# jtag-adapter-3-4.net
KiCad netlist of a schematic drawn in EAGLE
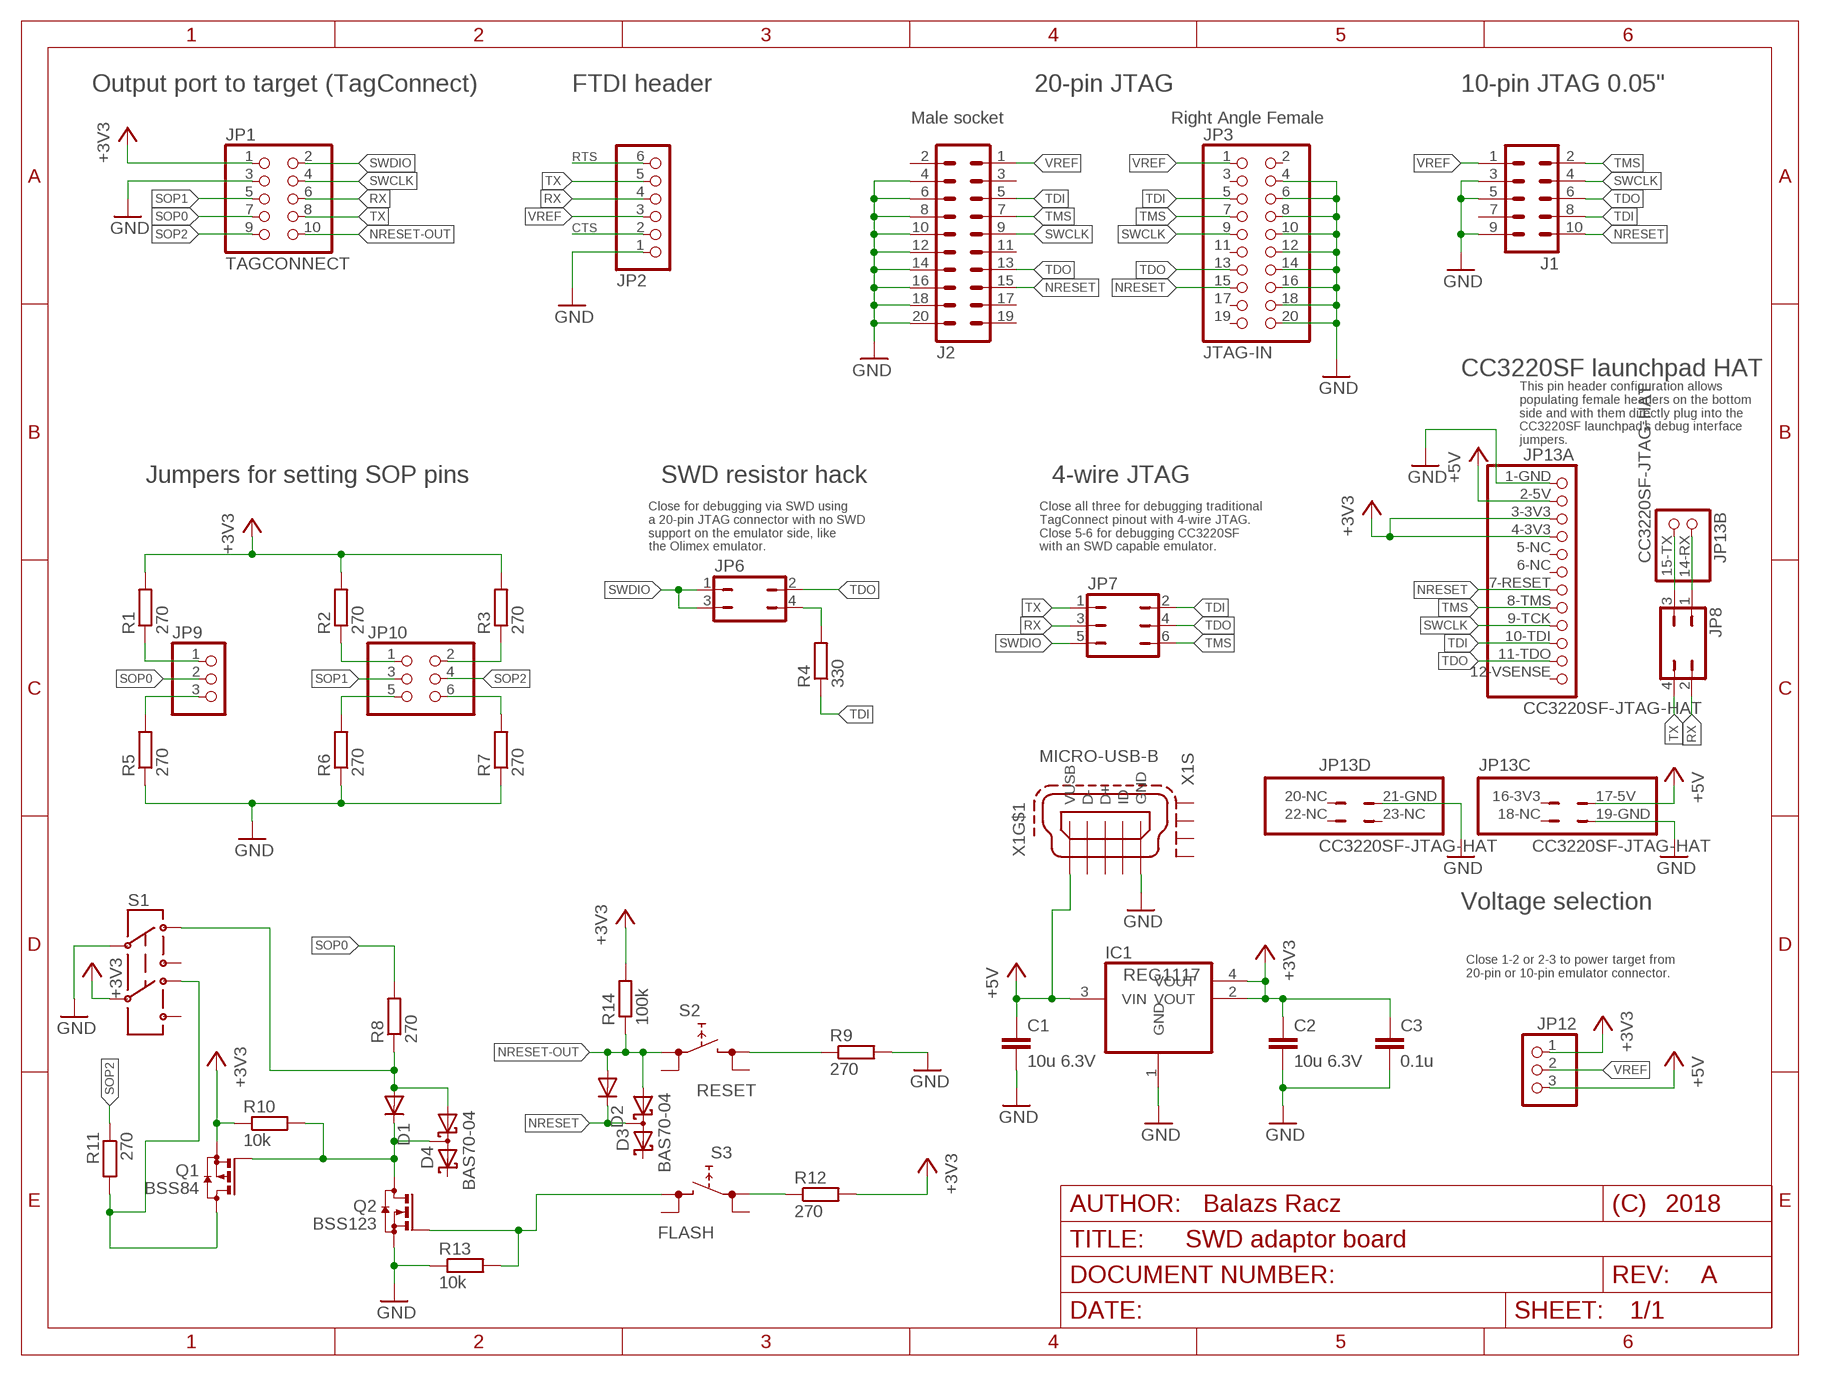
[diagram p0: schematic, sheet 1]

(export (version "E")
  (design (tool "Eeschema 10.0.6"))
  (components
    (comp (ref "C1")
      (value "10u 6.3V")
      (footprint "eagle-import:C0603K")
      (libsource (lib "eagle-import") (part "C-EUC0603K"))
    )
    (comp (ref "C2")
      (value "10u 6.3V")
      (footprint "eagle-import:C0603K")
      (libsource (lib "eagle-import") (part "C-EUC0603K"))
    )
    (comp (ref "C3")
      (value "0.1u")
      (footprint "eagle-import:C0603K")
      (libsource (lib "eagle-import") (part "C-EUC0603K"))
    )
    (comp (ref "D1")
      (value "DIODE-MINIMELF")
      (footprint "eagle-import:MINIMELF")
      (libsource (lib "eagle-import") (part "DIODE-MINIMELF"))
    )
    (comp (ref "D2")
      (value "DIODE-MINIMELF")
      (footprint "eagle-import:MINIMELF")
      (libsource (lib "eagle-import") (part "DIODE-MINIMELF"))
    )
    (comp (ref "D3")
      (value "BAS70-04")
      (footprint "eagle-import:SOT23")
      (libsource (lib "eagle-import") (part "BAS70-04"))
    )
    (comp (ref "D4")
      (value "BAS70-04")
      (footprint "eagle-import:SOT23")
      (libsource (lib "eagle-import") (part "BAS70-04"))
    )
    (comp (ref "IC1")
      (value "REG1117")
      (footprint "eagle-import:SOT223")
      (libsource (lib "eagle-import") (part "REG1117"))
    )
    (comp (ref "J1")
      (value "MA05-2_0.05X0.05")
      (footprint "eagle-import:MA05-2_0.05_X_0.05")
      (libsource (lib "eagle-import") (part "MA05-2_0.05X0.05"))
    )
    (comp (ref "J2")
      (value "MA10-2S")
      (footprint "eagle-import:MA10-2-SHROUDED")
      (libsource (lib "eagle-import") (part "MA10-2S"))
    )
    (comp (ref "JP1")
      (value "TAGCONNECT")
      (footprint "eagle-import:CON10M")
      (libsource (lib "eagle-import") (part "PINHD-2X5CN"))
    )
    (comp (ref "JP2")
      (value "PINHD-1X6")
      (footprint "eagle-import:1X06")
      (libsource (lib "eagle-import") (part "PINHD-1X6"))
    )
    (comp (ref "JP3")
      (value "JTAG-IN")
      (footprint "eagle-import:2X10")
      (libsource (lib "eagle-import") (part "PINHD-2X10"))
    )
    (comp (ref "JP6")
      (value "JP2Q")
      (footprint "eagle-import:JP2Q")
      (libsource (lib "eagle-import") (part "JP2Q"))
    )
    (comp (ref "JP7")
      (value "JP3Q")
      (footprint "eagle-import:JP3Q")
      (libsource (lib "eagle-import") (part "JP3Q"))
    )
    (comp (ref "JP8")
      (value "JP2Q")
      (footprint "eagle-import:JP2Q")
      (libsource (lib "eagle-import") (part "JP2Q"))
    )
    (comp (ref "JP9")
      (value "PINHD-1X3")
      (footprint "eagle-import:1X03")
      (libsource (lib "eagle-import") (part "PINHD-1X3"))
    )
    (comp (ref "JP10")
      (value "PINHD-2X3")
      (footprint "eagle-import:2X03")
      (libsource (lib "eagle-import") (part "PINHD-2X3"))
    )
    (comp (ref "JP12")
      (value "PINHD-1X3")
      (footprint "eagle-import:1X03")
      (libsource (lib "eagle-import") (part "PINHD-1X3"))
    )
    (comp (ref "JP13")
      (value "CC3220SF-JTAG-HAT")
      (footprint "eagle-import:JTAG-LAUNCHPAD-3220SF")
      (libsource (lib "eagle-import") (part "CC3220SF-JTAG-HAT"))
    )
    (comp (ref "Q1")
      (value "BSS84")
      (footprint "eagle-import:SOT23")
      (libsource (lib "eagle-import") (part "BSS84"))
    )
    (comp (ref "Q2")
      (value "BSS123")
      (footprint "eagle-import:SOT23")
      (libsource (lib "eagle-import") (part "BSS123"))
    )
    (comp (ref "R1")
      (value "270")
      (footprint "eagle-import:R0805")
      (libsource (lib "eagle-import") (part "R-EU_R0805"))
    )
    (comp (ref "R2")
      (value "270")
      (footprint "eagle-import:R0805")
      (libsource (lib "eagle-import") (part "R-EU_R0805"))
    )
    (comp (ref "R3")
      (value "270")
      (footprint "eagle-import:R0805")
      (libsource (lib "eagle-import") (part "R-EU_R0805"))
    )
    (comp (ref "R4")
      (value "330")
      (footprint "eagle-import:R0805")
      (libsource (lib "eagle-import") (part "R-EU_R0805"))
    )
    (comp (ref "R5")
      (value "270")
      (footprint "eagle-import:R0805")
      (libsource (lib "eagle-import") (part "R-EU_R0805"))
    )
    (comp (ref "R6")
      (value "270")
      (footprint "eagle-import:R0805")
      (libsource (lib "eagle-import") (part "R-EU_R0805"))
    )
    (comp (ref "R7")
      (value "270")
      (footprint "eagle-import:R0805")
      (libsource (lib "eagle-import") (part "R-EU_R0805"))
    )
    (comp (ref "R8")
      (value "270")
      (footprint "eagle-import:R0805")
      (libsource (lib "eagle-import") (part "R-EU_R0805"))
    )
    (comp (ref "R9")
      (value "270")
      (footprint "eagle-import:R0805")
      (libsource (lib "eagle-import") (part "R-EU_R0805"))
    )
    (comp (ref "R10")
      (value "10k")
      (footprint "eagle-import:R0805")
      (libsource (lib "eagle-import") (part "R-EU_R0805"))
    )
    (comp (ref "R11")
      (value "270")
      (footprint "eagle-import:R0805")
      (libsource (lib "eagle-import") (part "R-EU_R0805"))
    )
    (comp (ref "R12")
      (value "270")
      (footprint "eagle-import:R0805")
      (libsource (lib "eagle-import") (part "R-EU_R0805"))
    )
    (comp (ref "R13")
      (value "10k")
      (footprint "eagle-import:R0805")
      (libsource (lib "eagle-import") (part "R-EU_R0805"))
    )
    (comp (ref "R14")
      (value "100k")
      (footprint "eagle-import:R0805")
      (libsource (lib "eagle-import") (part "R-EU_R0805"))
    )
    (comp (ref "S1")
      (value "SWITCH-DPDTJS202011CQN")
      (footprint "eagle-import:DPDT-2.5X3.2MM")
      (libsource (lib "eagle-import") (part "SWITCH-DPDTJS202011CQN"))
    )
    (comp (ref "S2")
      (value "RESET")
      (footprint "eagle-import:TACTSW-6X6")
      (libsource (lib "eagle-import") (part "TACTSW-6X6S"))
    )
    (comp (ref "S3")
      (value "FLASH")
      (footprint "eagle-import:TACTSW-6X6")
      (libsource (lib "eagle-import") (part "TACTSW-6X6S"))
    )
    (comp (ref "X1")
      (value "MICRO-USB-B")
      (footprint "eagle-import:MICRO-B-PAC")
      (libsource (lib "eagle-import") (part "MICRO-USB-B"))
    )
  )
  (nets
    (net (code "1") (name "+3V3") (class "Default")
      (node (ref "C2") (pin "1") (pinfunction "1_1") (pintype "passive"))
      (node (ref "C3") (pin "1") (pinfunction "1_1") (pintype "passive"))
      (node (ref "IC1") (pin "2") (pinfunction "VOUT_2") (pintype "output"))
      (node (ref "IC1") (pin "4") (pinfunction "VOUT_4") (pintype "output"))
      (node (ref "JP1") (pin "1") (pinfunction "1_1") (pintype "passive"))
      (node (ref "JP12") (pin "1") (pinfunction "1_1") (pintype "passive"))
      (node (ref "JP13") (pin "3-3V3") (pinfunction "3_3-3V3") (pintype "passive"))
      (node (ref "JP13") (pin "4-3V3") (pinfunction "4_4-3V3") (pintype "passive"))
      (node (ref "Q1") (pin "2") (pinfunction "S_2") (pintype "passive"))
      (node (ref "R1") (pin "2") (pinfunction "2_2") (pintype "passive"))
      (node (ref "R10") (pin "1") (pinfunction "1_1") (pintype "passive"))
      (node (ref "R12") (pin "2") (pinfunction "2_2") (pintype "passive"))
      (node (ref "R14") (pin "2") (pinfunction "2_2") (pintype "passive"))
      (node (ref "R2") (pin "2") (pinfunction "2_2") (pintype "passive"))
      (node (ref "R3") (pin "2") (pinfunction "2_2") (pintype "passive"))
      (node (ref "S1") (pin "5") (pinfunction "2C_5") (pintype "bidirectional"))
    )
    (net (code "2") (name "+5V") (class "Default")
      (node (ref "C1") (pin "1") (pinfunction "1_1") (pintype "passive"))
      (node (ref "IC1") (pin "3") (pinfunction "VIN_3") (pintype "input"))
      (node (ref "JP12") (pin "3") (pinfunction "3_3") (pintype "passive"))
      (node (ref "JP13") (pin "17-5V") (pinfunction "2_17-5V") (pintype "passive"))
      (node (ref "JP13") (pin "2-5V") (pinfunction "2_2-5V") (pintype "passive"))
      (node (ref "X1") (pin "1") (pinfunction "VUSB_1") (pintype "passive"))
    )
    (net (code "3") (name "/CTS") (class "Default")
      (node (ref "JP2") (pin "2") (pinfunction "2_2") (pintype "passive"))
    )
    (net (code "4") (name "/RTS") (class "Default")
      (node (ref "JP2") (pin "6") (pinfunction "6_6") (pintype "passive"))
    )
    (net (code "5") (name "GND") (class "Default")
      (node (ref "C1") (pin "2") (pinfunction "2_2") (pintype "passive"))
      (node (ref "C2") (pin "2") (pinfunction "2_2") (pintype "passive"))
      (node (ref "C3") (pin "2") (pinfunction "2_2") (pintype "passive"))
      (node (ref "IC1") (pin "1") (pinfunction "GND_1") (pintype "power_in"))
      (node (ref "J1") (pin "3") (pinfunction "3_3") (pintype "passive"))
      (node (ref "J1") (pin "5") (pinfunction "5_5") (pintype "passive"))
      (node (ref "J1") (pin "9") (pinfunction "9_9") (pintype "passive"))
      (node (ref "J2") (pin "10") (pinfunction "10_10") (pintype "passive"))
      (node (ref "J2") (pin "12") (pinfunction "12_12") (pintype "passive"))
      (node (ref "J2") (pin "14") (pinfunction "14_14") (pintype "passive"))
      (node (ref "J2") (pin "16") (pinfunction "16_16") (pintype "passive"))
      (node (ref "J2") (pin "18") (pinfunction "18_18") (pintype "passive"))
      (node (ref "J2") (pin "20") (pinfunction "20_20") (pintype "passive"))
      (node (ref "J2") (pin "4") (pinfunction "4_4") (pintype "passive"))
      (node (ref "J2") (pin "6") (pinfunction "6_6") (pintype "passive"))
      (node (ref "J2") (pin "8") (pinfunction "8_8") (pintype "passive"))
      (node (ref "JP1") (pin "3") (pinfunction "3_3") (pintype "passive"))
      (node (ref "JP13") (pin "1-GND") (pinfunction "1_1-GND") (pintype "passive"))
      (node (ref "JP13") (pin "19-GND") (pinfunction "4_19-GND") (pintype "passive"))
      (node (ref "JP13") (pin "21-GND") (pinfunction "2_21-GND") (pintype "passive"))
      (node (ref "JP2") (pin "1") (pinfunction "1_1") (pintype "passive"))
      (node (ref "JP3") (pin "10") (pinfunction "10_10") (pintype "passive"))
      (node (ref "JP3") (pin "12") (pinfunction "12_12") (pintype "passive"))
      (node (ref "JP3") (pin "14") (pinfunction "14_14") (pintype "passive"))
      (node (ref "JP3") (pin "16") (pinfunction "16_16") (pintype "passive"))
      (node (ref "JP3") (pin "18") (pinfunction "18_18") (pintype "passive"))
      (node (ref "JP3") (pin "20") (pinfunction "20_20") (pintype "passive"))
      (node (ref "JP3") (pin "4") (pinfunction "4_4") (pintype "passive"))
      (node (ref "JP3") (pin "6") (pinfunction "6_6") (pintype "passive"))
      (node (ref "JP3") (pin "8") (pinfunction "8_8") (pintype "passive"))
      (node (ref "Q2") (pin "2") (pinfunction "S_2") (pintype "passive"))
      (node (ref "R13") (pin "1") (pinfunction "1_1") (pintype "passive"))
      (node (ref "R5") (pin "1") (pinfunction "1_1") (pintype "passive"))
      (node (ref "R6") (pin "1") (pinfunction "1_1") (pintype "passive"))
      (node (ref "R7") (pin "1") (pinfunction "1_1") (pintype "passive"))
      (node (ref "R9") (pin "2") (pinfunction "2_2") (pintype "passive"))
      (node (ref "S1") (pin "2") (pinfunction "1C_2") (pintype "bidirectional"))
      (node (ref "X1") (pin "5") (pinfunction "GND_5") (pintype "passive"))
    )
    (net (code "6") (name "NRESET") (class "Default")
      (node (ref "D2") (pin "C") (pinfunction "C_C") (pintype "passive"))
      (node (ref "D3") (pin "3") (pinfunction "C1A2_3") (pintype "passive"))
      (node (ref "J1") (pin "10") (pinfunction "10_10") (pintype "passive"))
      (node (ref "J2") (pin "15") (pinfunction "15_15") (pintype "passive"))
      (node (ref "JP13") (pin "7-RESET") (pinfunction "7_7-RESET") (pintype "passive"))
      (node (ref "JP3") (pin "15") (pinfunction "15_15") (pintype "passive"))
    )
    (net (code "7") (name "NRESET-OUT") (class "Default")
      (node (ref "D2") (pin "A") (pinfunction "A_A") (pintype "passive"))
      (node (ref "D3") (pin "1") (pinfunction "A1_1") (pintype "passive"))
      (node (ref "JP1") (pin "10") (pinfunction "10_10") (pintype "passive"))
      (node (ref "R14") (pin "1") (pinfunction "1_1") (pintype "passive"))
      (node (ref "S2") (pin "1") (pinfunction "1.1_1") (pintype "passive"))
    )
    (net (code "8") (name "Net-(D4-A1)") (class "Default")
      (node (ref "D1") (pin "A") (pinfunction "A_A") (pintype "passive"))
      (node (ref "D4") (pin "1") (pinfunction "A1_1") (pintype "passive"))
      (node (ref "R8") (pin "1") (pinfunction "1_1") (pintype "passive"))
      (node (ref "S1") (pin "1") (pinfunction "1A_1") (pintype "bidirectional"))
    )
    (net (code "9") (name "Net-(D4-C1A2)") (class "Default")
      (node (ref "D1") (pin "C") (pinfunction "C_C") (pintype "passive"))
      (node (ref "D4") (pin "3") (pinfunction "C1A2_3") (pintype "passive"))
      (node (ref "Q1") (pin "1") (pinfunction "G_1") (pintype "passive"))
      (node (ref "Q2") (pin "3") (pinfunction "D_3") (pintype "passive"))
      (node (ref "R10") (pin "2") (pinfunction "2_2") (pintype "passive"))
    )
    (net (code "10") (name "Net-(JP6-Pad4)") (class "Default")
      (node (ref "JP6") (pin "4") (pinfunction "4_4") (pintype "passive"))
      (node (ref "R4") (pin "2") (pinfunction "2_2") (pintype "passive"))
    )
    (net (code "11") (name "Net-(JP9-Pad1)") (class "Default")
      (node (ref "JP9") (pin "1") (pinfunction "1_1") (pintype "passive"))
      (node (ref "R1") (pin "1") (pinfunction "1_1") (pintype "passive"))
    )
    (net (code "12") (name "Net-(JP9-Pad3)") (class "Default")
      (node (ref "JP9") (pin "3") (pinfunction "3_3") (pintype "passive"))
      (node (ref "R5") (pin "2") (pinfunction "2_2") (pintype "passive"))
    )
    (net (code "13") (name "Net-(JP10-Pad1)") (class "Default")
      (node (ref "JP10") (pin "1") (pinfunction "1_1") (pintype "passive"))
      (node (ref "R2") (pin "1") (pinfunction "1_1") (pintype "passive"))
    )
    (net (code "14") (name "Net-(JP10-Pad2)") (class "Default")
      (node (ref "JP10") (pin "2") (pinfunction "2_2") (pintype "passive"))
      (node (ref "R3") (pin "1") (pinfunction "1_1") (pintype "passive"))
    )
    (net (code "15") (name "Net-(JP10-Pad5)") (class "Default")
      (node (ref "JP10") (pin "5") (pinfunction "5_5") (pintype "passive"))
      (node (ref "R6") (pin "2") (pinfunction "2_2") (pintype "passive"))
    )
    (net (code "16") (name "Net-(JP10-Pad6)") (class "Default")
      (node (ref "JP10") (pin "6") (pinfunction "6_6") (pintype "passive"))
      (node (ref "R7") (pin "2") (pinfunction "2_2") (pintype "passive"))
    )
    (net (code "17") (name "Net-(JP13B-1)") (class "Default")
      (node (ref "JP13") (pin "14-RX") (pinfunction "1_14-RX") (pintype "passive"))
      (node (ref "JP8") (pin "1") (pinfunction "1_1") (pintype "passive"))
    )
    (net (code "18") (name "Net-(JP13B-2)") (class "Default")
      (node (ref "JP13") (pin "15-TX") (pinfunction "2_15-TX") (pintype "passive"))
      (node (ref "JP8") (pin "3") (pinfunction "3_3") (pintype "passive"))
    )
    (net (code "19") (name "Net-(Q1-D)") (class "Default")
      (node (ref "Q1") (pin "3") (pinfunction "D_3") (pintype "passive"))
      (node (ref "R11") (pin "2") (pinfunction "2_2") (pintype "passive"))
      (node (ref "S1") (pin "4") (pinfunction "2A_4") (pintype "bidirectional"))
    )
    (net (code "20") (name "Net-(Q2-G)") (class "Default")
      (node (ref "Q2") (pin "1") (pinfunction "G_1") (pintype "passive"))
      (node (ref "R13") (pin "2") (pinfunction "2_2") (pintype "passive"))
      (node (ref "S3") (pin "3") (pinfunction "2.1_3") (pintype "passive"))
    )
    (net (code "21") (name "Net-(S2-2.1)") (class "Default")
      (node (ref "R9") (pin "1") (pinfunction "1_1") (pintype "passive"))
      (node (ref "S2") (pin "3") (pinfunction "2.1_3") (pintype "passive"))
    )
    (net (code "22") (name "Net-(S3-1.1)") (class "Default")
      (node (ref "R12") (pin "1") (pinfunction "1_1") (pintype "passive"))
      (node (ref "S3") (pin "1") (pinfunction "1.1_1") (pintype "passive"))
    )
    (net (code "23") (name "RX") (class "Default")
      (node (ref "JP1") (pin "6") (pinfunction "6_6") (pintype "passive"))
      (node (ref "JP2") (pin "4") (pinfunction "4_4") (pintype "passive"))
      (node (ref "JP7") (pin "3") (pinfunction "3_3") (pintype "passive"))
      (node (ref "JP8") (pin "2") (pinfunction "2_2") (pintype "passive"))
    )
    (net (code "24") (name "SOP0") (class "Default")
      (node (ref "JP1") (pin "7") (pinfunction "7_7") (pintype "passive"))
      (node (ref "JP9") (pin "2") (pinfunction "2_2") (pintype "passive"))
      (node (ref "R8") (pin "2") (pinfunction "2_2") (pintype "passive"))
    )
    (net (code "25") (name "SOP1") (class "Default")
      (node (ref "JP1") (pin "5") (pinfunction "5_5") (pintype "passive"))
      (node (ref "JP10") (pin "3") (pinfunction "3_3") (pintype "passive"))
    )
    (net (code "26") (name "SOP2") (class "Default")
      (node (ref "JP1") (pin "9") (pinfunction "9_9") (pintype "passive"))
      (node (ref "JP10") (pin "4") (pinfunction "4_4") (pintype "passive"))
      (node (ref "R11") (pin "1") (pinfunction "1_1") (pintype "passive"))
    )
    (net (code "27") (name "SWCLK") (class "Default")
      (node (ref "J1") (pin "4") (pinfunction "4_4") (pintype "passive"))
      (node (ref "J2") (pin "9") (pinfunction "9_9") (pintype "passive"))
      (node (ref "JP1") (pin "4") (pinfunction "4_4") (pintype "passive"))
      (node (ref "JP13") (pin "9-TCK") (pinfunction "9_9-TCK") (pintype "passive"))
      (node (ref "JP3") (pin "9") (pinfunction "9_9") (pintype "passive"))
    )
    (net (code "28") (name "SWDIO") (class "Default")
      (node (ref "JP1") (pin "2") (pinfunction "2_2") (pintype "passive"))
      (node (ref "JP6") (pin "1") (pinfunction "1_1") (pintype "passive"))
      (node (ref "JP6") (pin "3") (pinfunction "3_3") (pintype "passive"))
      (node (ref "JP7") (pin "5") (pinfunction "5_5") (pintype "passive"))
    )
    (net (code "29") (name "TDI") (class "Default")
      (node (ref "J1") (pin "8") (pinfunction "8_8") (pintype "passive"))
      (node (ref "J2") (pin "5") (pinfunction "5_5") (pintype "passive"))
      (node (ref "JP13") (pin "10-TDI") (pinfunction "10_10-TDI") (pintype "passive"))
      (node (ref "JP3") (pin "5") (pinfunction "5_5") (pintype "passive"))
      (node (ref "JP7") (pin "2") (pinfunction "2_2") (pintype "passive"))
      (node (ref "R4") (pin "1") (pinfunction "1_1") (pintype "passive"))
    )
    (net (code "30") (name "TDO") (class "Default")
      (node (ref "J1") (pin "6") (pinfunction "6_6") (pintype "passive"))
      (node (ref "J2") (pin "13") (pinfunction "13_13") (pintype "passive"))
      (node (ref "JP13") (pin "11-TDO") (pinfunction "11_11-TDO") (pintype "passive"))
      (node (ref "JP3") (pin "13") (pinfunction "13_13") (pintype "passive"))
      (node (ref "JP6") (pin "2") (pinfunction "2_2") (pintype "passive"))
      (node (ref "JP7") (pin "4") (pinfunction "4_4") (pintype "passive"))
    )
    (net (code "31") (name "TMS") (class "Default")
      (node (ref "J1") (pin "2") (pinfunction "2_2") (pintype "passive"))
      (node (ref "J2") (pin "7") (pinfunction "7_7") (pintype "passive"))
      (node (ref "JP13") (pin "8-TMS") (pinfunction "8_8-TMS") (pintype "passive"))
      (node (ref "JP3") (pin "7") (pinfunction "7_7") (pintype "passive"))
      (node (ref "JP7") (pin "6") (pinfunction "6_6") (pintype "passive"))
    )
    (net (code "32") (name "TX") (class "Default")
      (node (ref "JP1") (pin "8") (pinfunction "8_8") (pintype "passive"))
      (node (ref "JP2") (pin "5") (pinfunction "5_5") (pintype "passive"))
      (node (ref "JP7") (pin "1") (pinfunction "1_1") (pintype "passive"))
      (node (ref "JP8") (pin "4") (pinfunction "4_4") (pintype "passive"))
    )
    (net (code "33") (name "VREF") (class "Default")
      (node (ref "J1") (pin "1") (pinfunction "1_1") (pintype "passive"))
      (node (ref "J2") (pin "1") (pinfunction "1_1") (pintype "passive"))
      (node (ref "JP12") (pin "2") (pinfunction "2_2") (pintype "passive"))
      (node (ref "JP2") (pin "3") (pinfunction "3_3") (pintype "passive"))
      (node (ref "JP3") (pin "1") (pinfunction "1_1") (pintype "passive"))
    )
    (net (code "34") (name "unconnected-(D3-C2-Pad2)") (class "Default")
      (node (ref "D3") (pin "2") (pinfunction "C2_2") (pintype "passive"))
    )
    (net (code "35") (name "unconnected-(D4-C2-Pad2)") (class "Default")
      (node (ref "D4") (pin "2") (pinfunction "C2_2") (pintype "passive"))
    )
    (net (code "36") (name "unconnected-(J1-Pad7)") (class "Default")
      (node (ref "J1") (pin "7") (pinfunction "7_7") (pintype "passive"))
    )
    (net (code "37") (name "unconnected-(J2-Pad2)") (class "Default")
      (node (ref "J2") (pin "2") (pinfunction "2_2") (pintype "passive"))
    )
    (net (code "38") (name "unconnected-(J2-Pad3)") (class "Default")
      (node (ref "J2") (pin "3") (pinfunction "3_3") (pintype "passive"))
    )
    (net (code "39") (name "unconnected-(J2-Pad11)") (class "Default")
      (node (ref "J2") (pin "11") (pinfunction "11_11") (pintype "passive"))
    )
    (net (code "40") (name "unconnected-(J2-Pad17)") (class "Default")
      (node (ref "J2") (pin "17") (pinfunction "17_17") (pintype "passive"))
    )
    (net (code "41") (name "unconnected-(J2-Pad19)") (class "Default")
      (node (ref "J2") (pin "19") (pinfunction "19_19") (pintype "passive"))
    )
    (net (code "42") (name "unconnected-(JP3-Pad2)") (class "Default")
      (node (ref "JP3") (pin "2") (pinfunction "2_2") (pintype "passive"))
    )
    (net (code "43") (name "unconnected-(JP3-Pad3)") (class "Default")
      (node (ref "JP3") (pin "3") (pinfunction "3_3") (pintype "passive"))
    )
    (net (code "44") (name "unconnected-(JP3-Pad11)") (class "Default")
      (node (ref "JP3") (pin "11") (pinfunction "11_11") (pintype "passive"))
    )
    (net (code "45") (name "unconnected-(JP3-Pad17)") (class "Default")
      (node (ref "JP3") (pin "17") (pinfunction "17_17") (pintype "passive"))
    )
    (net (code "46") (name "unconnected-(JP3-Pad19)") (class "Default")
      (node (ref "JP3") (pin "19") (pinfunction "19_19") (pintype "passive"))
    )
    (net (code "47") (name "unconnected-(JP13A-5-Pad5-NC)") (class "Default")
      (node (ref "JP13") (pin "5-NC") (pinfunction "5_5-NC") (pintype "passive"))
    )
    (net (code "48") (name "unconnected-(JP13A-6-Pad6-NC)") (class "Default")
      (node (ref "JP13") (pin "6-NC") (pinfunction "6_6-NC") (pintype "passive"))
    )
    (net (code "49") (name "unconnected-(JP13A-12-Pad12-VSENSE)") (class "Default")
      (node (ref "JP13") (pin "12-VSENSE") (pinfunction "12_12-VSENSE") (pintype "passive"))
    )
    (net (code "50") (name "unconnected-(JP13C-1-Pad16-3V3)") (class "Default")
      (node (ref "JP13") (pin "16-3V3") (pinfunction "1_16-3V3") (pintype "passive"))
    )
    (net (code "51") (name "unconnected-(JP13C-3-Pad18-NC)") (class "Default")
      (node (ref "JP13") (pin "18-NC") (pinfunction "3_18-NC") (pintype "passive"))
    )
    (net (code "52") (name "unconnected-(JP13D-1-Pad20-NC)") (class "Default")
      (node (ref "JP13") (pin "20-NC") (pinfunction "1_20-NC") (pintype "passive"))
    )
    (net (code "53") (name "unconnected-(JP13D-3-Pad22-NC)") (class "Default")
      (node (ref "JP13") (pin "22-NC") (pinfunction "3_22-NC") (pintype "passive"))
    )
    (net (code "54") (name "unconnected-(JP13D-4-Pad23-NC)") (class "Default")
      (node (ref "JP13") (pin "23-NC") (pinfunction "4_23-NC") (pintype "passive"))
    )
    (net (code "55") (name "unconnected-(S1-1B-Pad3)") (class "Default")
      (node (ref "S1") (pin "3") (pinfunction "1B_3") (pintype "bidirectional"))
    )
    (net (code "56") (name "unconnected-(S1-2B-Pad6)") (class "Default")
      (node (ref "S1") (pin "6") (pinfunction "2B_6") (pintype "bidirectional"))
    )
    (net (code "57") (name "unconnected-(S2-1.2-Pad2)") (class "Default")
      (node (ref "S2") (pin "2") (pinfunction "1.2_2") (pintype "passive"))
    )
    (net (code "58") (name "unconnected-(S2-2.2-Pad4)") (class "Default")
      (node (ref "S2") (pin "4") (pinfunction "2.2_4") (pintype "passive"))
    )
    (net (code "59") (name "unconnected-(S3-1.2-Pad2)") (class "Default")
      (node (ref "S3") (pin "2") (pinfunction "1.2_2") (pintype "passive"))
    )
    (net (code "60") (name "unconnected-(S3-2.2-Pad4)") (class "Default")
      (node (ref "S3") (pin "4") (pinfunction "2.2_4") (pintype "passive"))
    )
    (net (code "61") (name "unconnected-(X1A-D+-Pad3)") (class "Default")
      (node (ref "X1") (pin "3") (pinfunction "D+_3") (pintype "passive"))
    )
    (net (code "62") (name "unconnected-(X1A-D--Pad2)") (class "Default")
      (node (ref "X1") (pin "2") (pinfunction "D-_2") (pintype "passive"))
    )
    (net (code "63") (name "unconnected-(X1A-ID-Pad4)") (class "Default")
      (node (ref "X1") (pin "4") (pinfunction "ID_4") (pintype "passive"))
    )
    (net (code "64") (name "unconnected-(X1B-S1-PadM1)") (class "Default")
      (node (ref "X1") (pin "M1") (pinfunction "S1_M1") (pintype "passive"))
    )
    (net (code "65") (name "unconnected-(X1B-S2-PadM2)") (class "Default")
      (node (ref "X1") (pin "M2") (pinfunction "S2_M2") (pintype "passive"))
    )
    (net (code "66") (name "unconnected-(X1B-S3-PadM3)") (class "Default")
      (node (ref "X1") (pin "M3") (pinfunction "S3_M3") (pintype "passive"))
    )
    (net (code "67") (name "unconnected-(X1B-S4-PadM4)") (class "Default")
      (node (ref "X1") (pin "M4") (pinfunction "S4_M4") (pintype "passive"))
    )
  )
)
